# FPGA_IO.net
KiCad netlist of a schematic drawn in Altium Designer
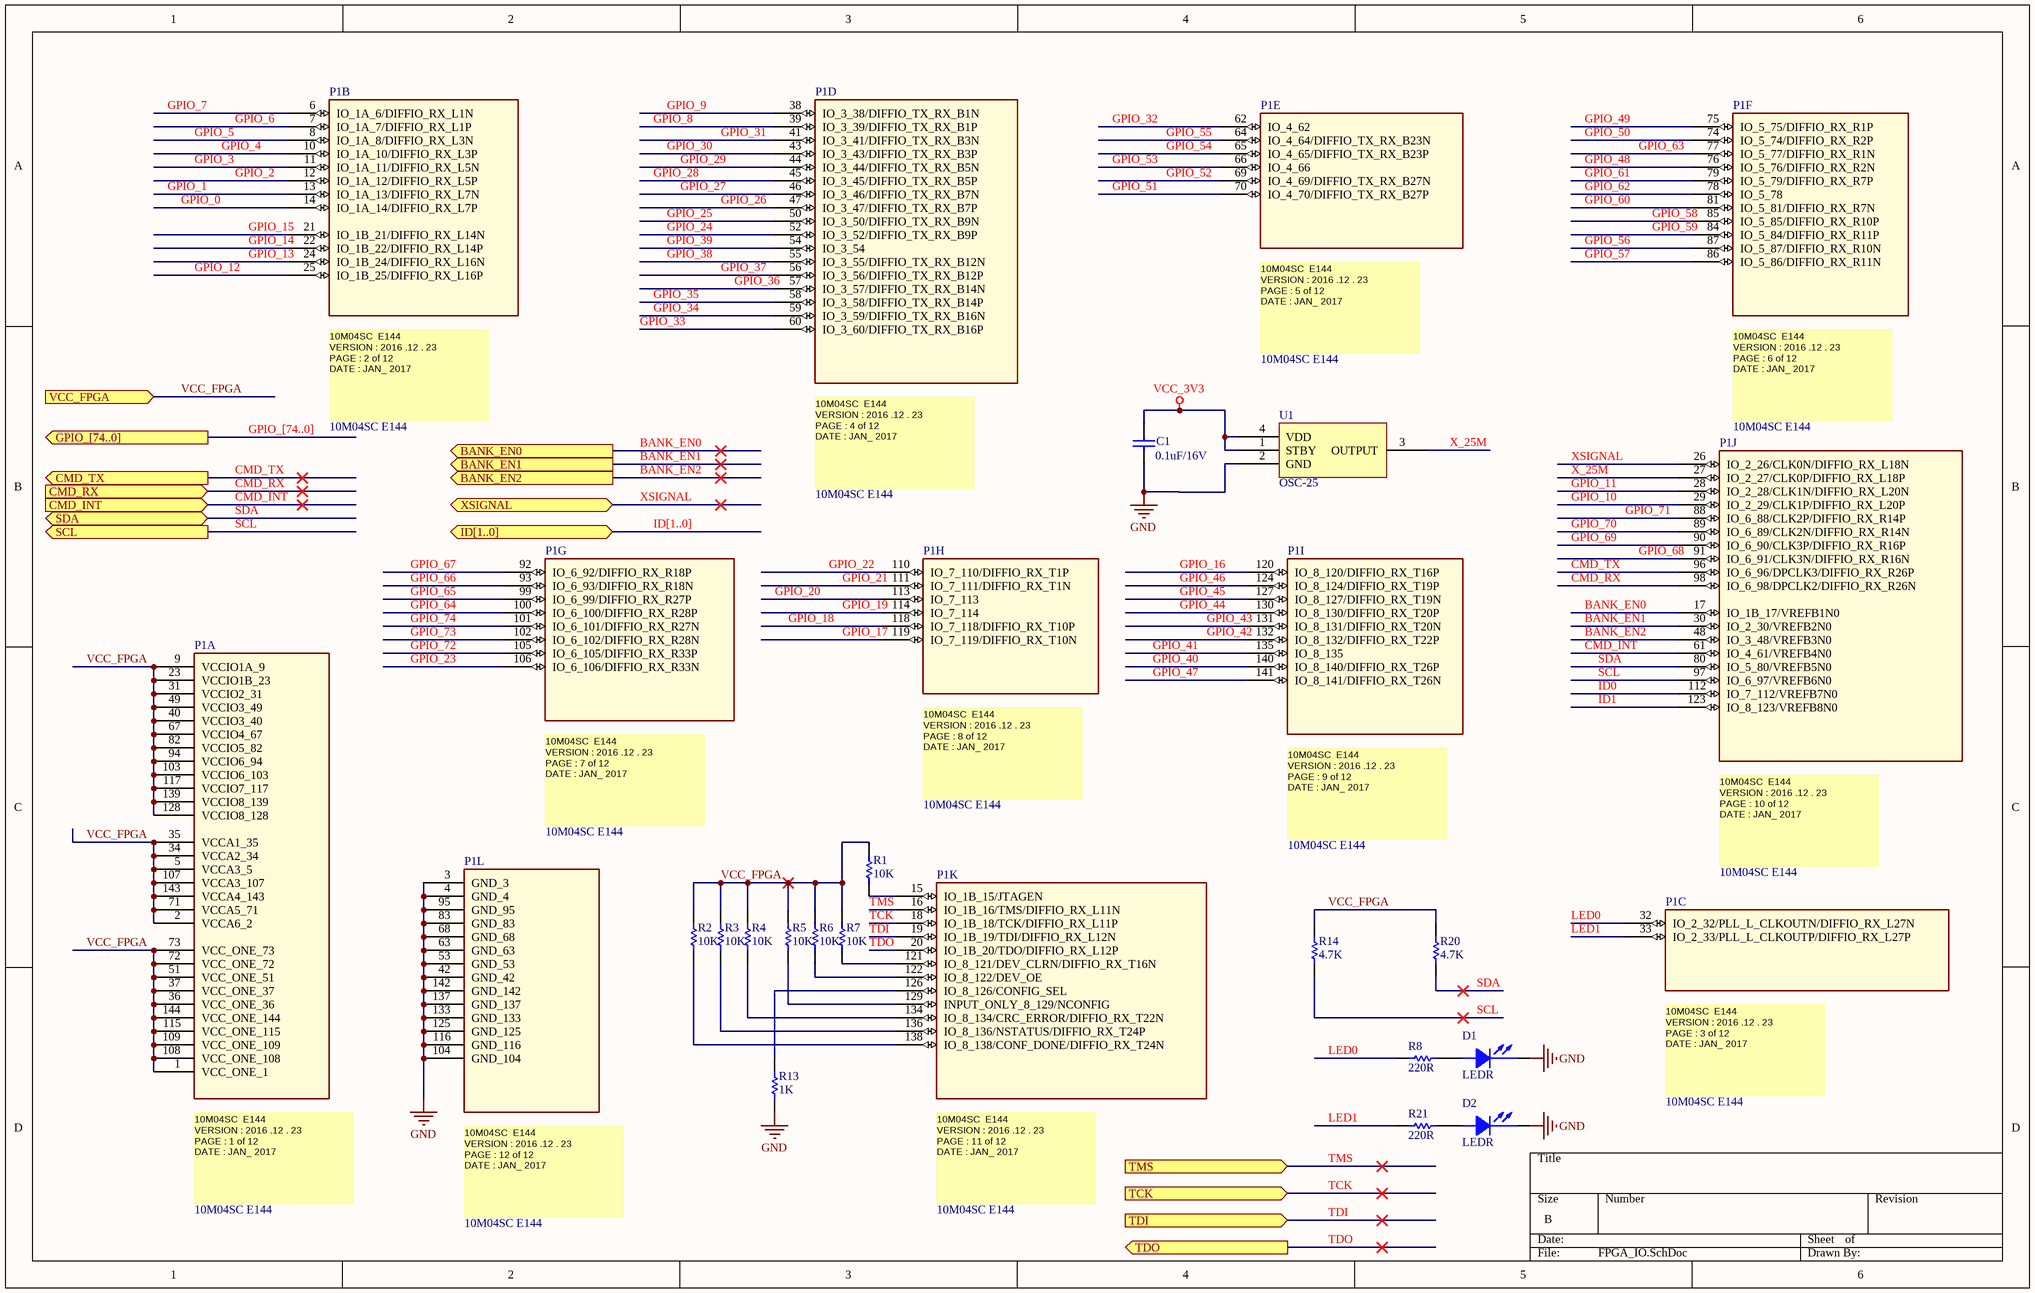
[diagram p0: FPGA_IO.SchDoc]

(export (version "E")
  (design (tool "Eeschema 10.0.6"))
  (components
    (comp (ref "C1")
      (value "0.1uF/16V")
      (footprint "0603C")
      (description "Multilayer Ceramic Capacitors MLCC - SMD/SMT 0603 16VDC 0.1uF 10% X7R AEC-Q200")
      (fields (field (name "MFR") "Taiyo Yuden") (field (name "MFR PART NO") "EMK107B7104KAHT"))
      (libsource (lib "Miscellaneous Devices") (part "Cap"))
    )
    (comp (ref "D1")
      (value "LEDR")
      (footprint "LED_0603")
      (description "Standard LEDs - SMD Red 631nm 14mcd 5mA")
      (fields (field (name "MFR") "Lite-On") (field (name "MFR PART NO") "LTST-C193KRKT-5A"))
      (libsource (lib "de20") (part "LED"))
    )
    (comp (ref "D2")
      (value "LEDR")
      (footprint "LED_0603")
      (description "Standard LEDs - SMD Red 631nm 14mcd 5mA")
      (fields (field (name "MFR") "Lite-On") (field (name "MFR PART NO") "LTST-C193KRKT-5A"))
      (libsource (lib "de20") (part "LED"))
    )
    (comp (ref "P1")
      (value "10M04SC E144")
      (footprint "10M04SCE144C8G")
      (description "FPGA - Field Programmable Gate Array non-volatile FPGA, 101 I/O, 144EQFP")
      (fields (field (name "MFR") "Intel / Altera") (field (name "MFR PART NO") "10M04SCE144C8G"))
      (libsource (lib "10m04sc_Library") (part "10M04SC E144"))
    )
    (comp (ref "R1")
      (value "10K")
      (footprint "0603R")
      (description "Thick Film Resistors - SMD 0603 10Kohms 1% Anti-Sulfur AEC-Q200")
      (fields (field (name "MFR") "ROHM Semiconductor") (field (name "MFR PART NO") "SFR03EZPF1002"))
      (libsource (lib "Miscellaneous Devices") (part "Res1"))
    )
    (comp (ref "R2")
      (value "10K")
      (footprint "0603R")
      (description "Thick Film Resistors - SMD 0603 10Kohms 1% Anti-Sulfur AEC-Q200")
      (fields (field (name "MFR") "ROHM Semiconductor") (field (name "MFR PART NO") "SFR03EZPF1002"))
      (libsource (lib "Miscellaneous Devices") (part "Res1"))
    )
    (comp (ref "R3")
      (value "10K")
      (footprint "0603R")
      (description "Thick Film Resistors - SMD 0603 10Kohms 1% Anti-Sulfur AEC-Q200")
      (fields (field (name "MFR") "ROHM Semiconductor") (field (name "MFR PART NO") "SFR03EZPF1002"))
      (libsource (lib "Miscellaneous Devices") (part "Res1"))
    )
    (comp (ref "R4")
      (value "10K")
      (footprint "0603R")
      (description "Thick Film Resistors - SMD 0603 10Kohms 1% Anti-Sulfur AEC-Q200")
      (fields (field (name "MFR") "ROHM Semiconductor") (field (name "MFR PART NO") "SFR03EZPF1002"))
      (libsource (lib "Miscellaneous Devices") (part "Res1"))
    )
    (comp (ref "R5")
      (value "10K")
      (footprint "0603R")
      (description "Thick Film Resistors - SMD 0603 10Kohms 1% Anti-Sulfur AEC-Q200")
      (fields (field (name "MFR") "ROHM Semiconductor") (field (name "MFR PART NO") "SFR03EZPF1002"))
      (libsource (lib "Miscellaneous Devices") (part "Res1"))
    )
    (comp (ref "R6")
      (value "10K")
      (footprint "0603R")
      (description "Thick Film Resistors - SMD 0603 10Kohms 1% Anti-Sulfur AEC-Q200")
      (fields (field (name "MFR") "ROHM Semiconductor") (field (name "MFR PART NO") "SFR03EZPF1002"))
      (libsource (lib "Miscellaneous Devices") (part "Res1"))
    )
    (comp (ref "R7")
      (value "10K")
      (footprint "0603R")
      (description "Thick Film Resistors - SMD 0603 10Kohms 1% Anti-Sulfur AEC-Q200")
      (fields (field (name "MFR") "ROHM Semiconductor") (field (name "MFR PART NO") "SFR03EZPF1002"))
      (libsource (lib "Miscellaneous Devices") (part "Res1"))
    )
    (comp (ref "R8")
      (value "220R")
      (footprint "0603R")
      (description "Thick Film Resistors - SMD 1/10Watt 220ohms 5% Commercial Use")
      (fields (field (name "MFR") "Vishay / Dale") (field (name "MFR PART NO") "CRCW0603220RJNEAC"))
      (libsource (lib "Miscellaneous Devices") (part "Res1"))
    )
    (comp (ref "R13")
      (value "1K")
      (footprint "0603R")
      (description "Resistor")
      (fields (field (name "MFR") "Vishay / Dale") (field (name "MFR PART NO") "CRCW06031K00FKEAC"))
      (libsource (lib "Miscellaneous Devices") (part "Res1"))
    )
    (comp (ref "R14")
      (value "4.7K")
      (footprint "0603R")
      (description "Thick Film Resistors - SMD 1/10Watt 4.7Kohms 5% Commercial Use")
      (fields (field (name "MFR") "Vishay / Dale") (field (name "MFR PART NO") "CRCW06034K70JNEAC"))
      (libsource (lib "Miscellaneous Devices") (part "Res1"))
    )
    (comp (ref "R20")
      (value "4.7K")
      (footprint "0603R")
      (description "Thick Film Resistors - SMD 1/10Watt 4.7Kohms 5% Commercial Use")
      (fields (field (name "MFR") "Vishay / Dale") (field (name "MFR PART NO") "CRCW06034K70JNEAC"))
      (libsource (lib "Miscellaneous Devices") (part "Res1"))
    )
    (comp (ref "R21")
      (value "220R")
      (footprint "0603R")
      (description "Thick Film Resistors - SMD 1/10Watt 220ohms 5% Commercial Use")
      (fields (field (name "MFR") "Vishay / Dale") (field (name "MFR PART NO") "CRCW0603220RJNEAC"))
      (libsource (lib "Miscellaneous Devices") (part "Res1"))
    )
    (comp (ref "U1")
      (value "OSC-25")
      (footprint "ASE-25.000MHZ-LC-T")
      (description "Standard Clock Oscillators 25.0 MHZ 3.3V 50PPM SMD 32")
      (fields (field (name "MFR") "ABRACON") (field (name "MFR PART NO") "ASE-25.000MHZ-LC-T"))
      (libsource (lib "Schlib1") (part "CRYSTAL"))
    )
  )
  (nets
    (net (code "1") (name "/BANK_EN0") (class "Default")
      (node (ref "P1") (pin "17") (pinfunction "IO_1B_17/VREFB1N0_17") (pintype "bidirectional"))
    )
    (net (code "2") (name "/BANK_EN1") (class "Default")
      (node (ref "P1") (pin "30") (pinfunction "IO_2_30/VREFB2N0_30") (pintype "bidirectional"))
    )
    (net (code "3") (name "/BANK_EN2") (class "Default")
      (node (ref "P1") (pin "48") (pinfunction "IO_3_48/VREFB3N0_48") (pintype "bidirectional"))
    )
    (net (code "4") (name "/CMD_INT") (class "Default")
      (node (ref "P1") (pin "61") (pinfunction "IO_4_61/VREFB4N0_61") (pintype "bidirectional"))
    )
    (net (code "5") (name "/CMD_RX") (class "Default")
      (node (ref "P1") (pin "98") (pinfunction "IO_6_98/DPCLK2/DIFFIO_RX_R26N_98") (pintype "bidirectional"))
    )
    (net (code "6") (name "/CMD_TX") (class "Default")
      (node (ref "P1") (pin "96") (pinfunction "IO_6_96/DPCLK3/DIFFIO_RX_R26P_96") (pintype "bidirectional"))
    )
    (net (code "7") (name "/GPIO_0") (class "Default")
      (node (ref "P1") (pin "14") (pinfunction "IO_1A_14/DIFFIO_RX_L7P_14") (pintype "bidirectional"))
    )
    (net (code "8") (name "/GPIO_1") (class "Default")
      (node (ref "P1") (pin "13") (pinfunction "IO_1A_13/DIFFIO_RX_L7N_13") (pintype "bidirectional"))
    )
    (net (code "9") (name "/GPIO_2") (class "Default")
      (node (ref "P1") (pin "12") (pinfunction "IO_1A_12/DIFFIO_RX_L5P_12") (pintype "bidirectional"))
    )
    (net (code "10") (name "/GPIO_3") (class "Default")
      (node (ref "P1") (pin "11") (pinfunction "IO_1A_11/DIFFIO_RX_L5N_11") (pintype "bidirectional"))
    )
    (net (code "11") (name "/GPIO_4") (class "Default")
      (node (ref "P1") (pin "10") (pinfunction "IO_1A_10/DIFFIO_RX_L3P_10") (pintype "bidirectional"))
    )
    (net (code "12") (name "/GPIO_5") (class "Default")
      (node (ref "P1") (pin "8") (pinfunction "IO_1A_8/DIFFIO_RX_L3N_8") (pintype "bidirectional"))
    )
    (net (code "13") (name "/GPIO_6") (class "Default")
      (node (ref "P1") (pin "7") (pinfunction "IO_1A_7/DIFFIO_RX_L1P_7") (pintype "bidirectional"))
    )
    (net (code "14") (name "/GPIO_7") (class "Default")
      (node (ref "P1") (pin "6") (pinfunction "IO_1A_6/DIFFIO_RX_L1N_6") (pintype "bidirectional"))
    )
    (net (code "15") (name "/GPIO_8") (class "Default")
      (node (ref "P1") (pin "39") (pinfunction "IO_3_39/DIFFIO_TX_RX_B1P_39") (pintype "bidirectional"))
    )
    (net (code "16") (name "/GPIO_9") (class "Default")
      (node (ref "P1") (pin "38") (pinfunction "IO_3_38/DIFFIO_TX_RX_B1N_38") (pintype "bidirectional"))
    )
    (net (code "17") (name "/GPIO_10") (class "Default")
      (node (ref "P1") (pin "29") (pinfunction "IO_2_29/CLK1P/DIFFIO_RX_L20P_29") (pintype "bidirectional"))
    )
    (net (code "18") (name "/GPIO_11") (class "Default")
      (node (ref "P1") (pin "28") (pinfunction "IO_2_28/CLK1N/DIFFIO_RX_L20N_28") (pintype "bidirectional"))
    )
    (net (code "19") (name "/GPIO_12") (class "Default")
      (node (ref "P1") (pin "25") (pinfunction "IO_1B_25/DIFFIO_RX_L16P_25") (pintype "bidirectional"))
    )
    (net (code "20") (name "/GPIO_13") (class "Default")
      (node (ref "P1") (pin "24") (pinfunction "IO_1B_24/DIFFIO_RX_L16N_24") (pintype "bidirectional"))
    )
    (net (code "21") (name "/GPIO_14") (class "Default")
      (node (ref "P1") (pin "22") (pinfunction "IO_1B_22/DIFFIO_RX_L14P_22") (pintype "bidirectional"))
    )
    (net (code "22") (name "/GPIO_15") (class "Default")
      (node (ref "P1") (pin "21") (pinfunction "IO_1B_21/DIFFIO_RX_L14N_21") (pintype "bidirectional"))
    )
    (net (code "23") (name "/GPIO_16") (class "Default")
      (node (ref "P1") (pin "120") (pinfunction "IO_8_120/DIFFIO_RX_T16P_120") (pintype "bidirectional"))
    )
    (net (code "24") (name "/GPIO_17") (class "Default")
      (node (ref "P1") (pin "119") (pinfunction "IO_7_119/DIFFIO_RX_T10N_119") (pintype "bidirectional"))
    )
    (net (code "25") (name "/GPIO_18") (class "Default")
      (node (ref "P1") (pin "118") (pinfunction "IO_7_118/DIFFIO_RX_T10P_118") (pintype "bidirectional"))
    )
    (net (code "26") (name "/GPIO_19") (class "Default")
      (node (ref "P1") (pin "114") (pinfunction "IO_7_114_114") (pintype "bidirectional"))
    )
    (net (code "27") (name "/GPIO_20") (class "Default")
      (node (ref "P1") (pin "113") (pinfunction "IO_7_113_113") (pintype "bidirectional"))
    )
    (net (code "28") (name "/GPIO_21") (class "Default")
      (node (ref "P1") (pin "111") (pinfunction "IO_7_111/DIFFIO_RX_T1N_111") (pintype "bidirectional"))
    )
    (net (code "29") (name "/GPIO_22") (class "Default")
      (node (ref "P1") (pin "110") (pinfunction "IO_7_110/DIFFIO_RX_T1P_110") (pintype "bidirectional"))
    )
    (net (code "30") (name "/GPIO_23") (class "Default")
      (node (ref "P1") (pin "106") (pinfunction "IO_6_106/DIFFIO_RX_R33N_106") (pintype "bidirectional"))
    )
    (net (code "31") (name "/GPIO_24") (class "Default")
      (node (ref "P1") (pin "52") (pinfunction "IO_3_52/DIFFIO_TX_RX_B9P_52") (pintype "bidirectional"))
    )
    (net (code "32") (name "/GPIO_25") (class "Default")
      (node (ref "P1") (pin "50") (pinfunction "IO_3_50/DIFFIO_TX_RX_B9N_50") (pintype "bidirectional"))
    )
    (net (code "33") (name "/GPIO_26") (class "Default")
      (node (ref "P1") (pin "47") (pinfunction "IO_3_47/DIFFIO_TX_RX_B7P_47") (pintype "bidirectional"))
    )
    (net (code "34") (name "/GPIO_27") (class "Default")
      (node (ref "P1") (pin "46") (pinfunction "IO_3_46/DIFFIO_TX_RX_B7N_46") (pintype "bidirectional"))
    )
    (net (code "35") (name "/GPIO_28") (class "Default")
      (node (ref "P1") (pin "45") (pinfunction "IO_3_45/DIFFIO_TX_RX_B5P_45") (pintype "bidirectional"))
    )
    (net (code "36") (name "/GPIO_29") (class "Default")
      (node (ref "P1") (pin "44") (pinfunction "IO_3_44/DIFFIO_TX_RX_B5N_44") (pintype "bidirectional"))
    )
    (net (code "37") (name "/GPIO_30") (class "Default")
      (node (ref "P1") (pin "43") (pinfunction "IO_3_43/DIFFIO_TX_RX_B3P_43") (pintype "bidirectional"))
    )
    (net (code "38") (name "/GPIO_31") (class "Default")
      (node (ref "P1") (pin "41") (pinfunction "IO_3_41/DIFFIO_TX_RX_B3N_41") (pintype "bidirectional"))
    )
    (net (code "39") (name "/GPIO_32") (class "Default")
      (node (ref "P1") (pin "62") (pinfunction "IO_4_62_62") (pintype "bidirectional"))
    )
    (net (code "40") (name "/GPIO_33") (class "Default")
      (node (ref "P1") (pin "60") (pinfunction "IO_3_60/DIFFIO_TX_RX_B16P_60") (pintype "bidirectional"))
    )
    (net (code "41") (name "/GPIO_34") (class "Default")
      (node (ref "P1") (pin "59") (pinfunction "IO_3_59/DIFFIO_TX_RX_B16N_59") (pintype "bidirectional"))
    )
    (net (code "42") (name "/GPIO_35") (class "Default")
      (node (ref "P1") (pin "58") (pinfunction "IO_3_58/DIFFIO_TX_RX_B14P_58") (pintype "bidirectional"))
    )
    (net (code "43") (name "/GPIO_36") (class "Default")
      (node (ref "P1") (pin "57") (pinfunction "IO_3_57/DIFFIO_TX_RX_B14N_57") (pintype "bidirectional"))
    )
    (net (code "44") (name "/GPIO_37") (class "Default")
      (node (ref "P1") (pin "56") (pinfunction "IO_3_56/DIFFIO_TX_RX_B12P_56") (pintype "bidirectional"))
    )
    (net (code "45") (name "/GPIO_38") (class "Default")
      (node (ref "P1") (pin "55") (pinfunction "IO_3_55/DIFFIO_TX_RX_B12N_55") (pintype "bidirectional"))
    )
    (net (code "46") (name "/GPIO_39") (class "Default")
      (node (ref "P1") (pin "54") (pinfunction "IO_3_54_54") (pintype "bidirectional"))
    )
    (net (code "47") (name "/GPIO_40") (class "Default")
      (node (ref "P1") (pin "140") (pinfunction "IO_8_140/DIFFIO_RX_T26P_140") (pintype "bidirectional"))
    )
    (net (code "48") (name "/GPIO_41") (class "Default")
      (node (ref "P1") (pin "135") (pinfunction "IO_8_135_135") (pintype "bidirectional"))
    )
    (net (code "49") (name "/GPIO_42") (class "Default")
      (node (ref "P1") (pin "132") (pinfunction "IO_8_132/DIFFIO_RX_T22P_132") (pintype "bidirectional"))
    )
    (net (code "50") (name "/GPIO_43") (class "Default")
      (node (ref "P1") (pin "131") (pinfunction "IO_8_131/DIFFIO_RX_T20N_131") (pintype "bidirectional"))
    )
    (net (code "51") (name "/GPIO_44") (class "Default")
      (node (ref "P1") (pin "130") (pinfunction "IO_8_130/DIFFIO_RX_T20P_130") (pintype "bidirectional"))
    )
    (net (code "52") (name "/GPIO_45") (class "Default")
      (node (ref "P1") (pin "127") (pinfunction "IO_8_127/DIFFIO_RX_T19N_127") (pintype "bidirectional"))
    )
    (net (code "53") (name "/GPIO_46") (class "Default")
      (node (ref "P1") (pin "124") (pinfunction "IO_8_124/DIFFIO_RX_T19P_124") (pintype "bidirectional"))
    )
    (net (code "54") (name "/GPIO_47") (class "Default")
      (node (ref "P1") (pin "141") (pinfunction "IO_8_141/DIFFIO_RX_T26N_141") (pintype "bidirectional"))
    )
    (net (code "55") (name "/GPIO_48") (class "Default")
      (node (ref "P1") (pin "76") (pinfunction "IO_5_76/DIFFIO_RX_R2N_76") (pintype "bidirectional"))
    )
    (net (code "56") (name "/GPIO_49") (class "Default")
      (node (ref "P1") (pin "75") (pinfunction "IO_5_75/DIFFIO_RX_R1P_75") (pintype "bidirectional"))
    )
    (net (code "57") (name "/GPIO_50") (class "Default")
      (node (ref "P1") (pin "74") (pinfunction "IO_5_74/DIFFIO_RX_R2P_74") (pintype "bidirectional"))
    )
    (net (code "58") (name "/GPIO_51") (class "Default")
      (node (ref "P1") (pin "70") (pinfunction "IO_4_70/DIFFIO_TX_RX_B27P_70") (pintype "bidirectional"))
    )
    (net (code "59") (name "/GPIO_52") (class "Default")
      (node (ref "P1") (pin "69") (pinfunction "IO_4_69/DIFFIO_TX_RX_B27N_69") (pintype "bidirectional"))
    )
    (net (code "60") (name "/GPIO_53") (class "Default")
      (node (ref "P1") (pin "66") (pinfunction "IO_4_66_66") (pintype "bidirectional"))
    )
    (net (code "61") (name "/GPIO_54") (class "Default")
      (node (ref "P1") (pin "65") (pinfunction "IO_4_65/DIFFIO_TX_RX_B23P_65") (pintype "bidirectional"))
    )
    (net (code "62") (name "/GPIO_55") (class "Default")
      (node (ref "P1") (pin "64") (pinfunction "IO_4_64/DIFFIO_TX_RX_B23N_64") (pintype "bidirectional"))
    )
    (net (code "63") (name "/GPIO_56") (class "Default")
      (node (ref "P1") (pin "87") (pinfunction "IO_5_87/DIFFIO_RX_R10N_87") (pintype "bidirectional"))
    )
    (net (code "64") (name "/GPIO_57") (class "Default")
      (node (ref "P1") (pin "86") (pinfunction "IO_5_86/DIFFIO_RX_R11N_86") (pintype "bidirectional"))
    )
    (net (code "65") (name "/GPIO_58") (class "Default")
      (node (ref "P1") (pin "85") (pinfunction "IO_5_85/DIFFIO_RX_R10P_85") (pintype "bidirectional"))
    )
    (net (code "66") (name "/GPIO_59") (class "Default")
      (node (ref "P1") (pin "84") (pinfunction "IO_5_84/DIFFIO_RX_R11P_84") (pintype "bidirectional"))
    )
    (net (code "67") (name "/GPIO_60") (class "Default")
      (node (ref "P1") (pin "81") (pinfunction "IO_5_81/DIFFIO_RX_R7N_81") (pintype "bidirectional"))
    )
    (net (code "68") (name "/GPIO_61") (class "Default")
      (node (ref "P1") (pin "79") (pinfunction "IO_5_79/DIFFIO_RX_R7P_79") (pintype "bidirectional"))
    )
    (net (code "69") (name "/GPIO_62") (class "Default")
      (node (ref "P1") (pin "78") (pinfunction "IO_5_78_78") (pintype "bidirectional"))
    )
    (net (code "70") (name "/GPIO_63") (class "Default")
      (node (ref "P1") (pin "77") (pinfunction "IO_5_77/DIFFIO_RX_R1N_77") (pintype "bidirectional"))
    )
    (net (code "71") (name "/GPIO_64") (class "Default")
      (node (ref "P1") (pin "100") (pinfunction "IO_6_100/DIFFIO_RX_R28P_100") (pintype "bidirectional"))
    )
    (net (code "72") (name "/GPIO_65") (class "Default")
      (node (ref "P1") (pin "99") (pinfunction "IO_6_99/DIFFIO_RX_R27P_99") (pintype "bidirectional"))
    )
    (net (code "73") (name "/GPIO_66") (class "Default")
      (node (ref "P1") (pin "93") (pinfunction "IO_6_93/DIFFIO_RX_R18N_93") (pintype "bidirectional"))
    )
    (net (code "74") (name "/GPIO_67") (class "Default")
      (node (ref "P1") (pin "92") (pinfunction "IO_6_92/DIFFIO_RX_R18P_92") (pintype "bidirectional"))
    )
    (net (code "75") (name "/GPIO_68") (class "Default")
      (node (ref "P1") (pin "91") (pinfunction "IO_6_91/CLK3N/DIFFIO_RX_R16N_91") (pintype "bidirectional"))
    )
    (net (code "76") (name "/GPIO_69") (class "Default")
      (node (ref "P1") (pin "90") (pinfunction "IO_6_90/CLK3P/DIFFIO_RX_R16P_90") (pintype "bidirectional"))
    )
    (net (code "77") (name "/GPIO_70") (class "Default")
      (node (ref "P1") (pin "89") (pinfunction "IO_6_89/CLK2N/DIFFIO_RX_R14N_89") (pintype "bidirectional"))
    )
    (net (code "78") (name "/GPIO_71") (class "Default")
      (node (ref "P1") (pin "88") (pinfunction "IO_6_88/CLK2P/DIFFIO_RX_R14P_88") (pintype "bidirectional"))
    )
    (net (code "79") (name "/GPIO_72") (class "Default")
      (node (ref "P1") (pin "105") (pinfunction "IO_6_105/DIFFIO_RX_R33P_105") (pintype "bidirectional"))
    )
    (net (code "80") (name "/GPIO_73") (class "Default")
      (node (ref "P1") (pin "102") (pinfunction "IO_6_102/DIFFIO_RX_R28N_102") (pintype "bidirectional"))
    )
    (net (code "81") (name "/GPIO_74") (class "Default")
      (node (ref "P1") (pin "101") (pinfunction "IO_6_101/DIFFIO_RX_R27N_101") (pintype "bidirectional"))
    )
    (net (code "83") (name "/ID0") (class "Default")
      (node (ref "P1") (pin "112") (pinfunction "IO_7_112/VREFB7N0_112") (pintype "bidirectional"))
    )
    (net (code "84") (name "/ID1") (class "Default")
      (node (ref "P1") (pin "123") (pinfunction "IO_8_123/VREFB8N0_123") (pintype "bidirectional"))
    )
    (net (code "86") (name "/LED0") (class "Default")
      (node (ref "P1") (pin "32") (pinfunction "IO_2_32/PLL_L_CLKOUTN/DIFFIO_RX_L27N_32") (pintype "bidirectional"))
      (node (ref "R8") (pin "2") (pinfunction "2_2") (pintype "passive"))
    )
    (net (code "87") (name "/LED1") (class "Default")
      (node (ref "P1") (pin "33") (pinfunction "IO_2_33/PLL_L_CLKOUTP/DIFFIO_RX_L27P_33") (pintype "bidirectional"))
      (node (ref "R21") (pin "2") (pinfunction "2_2") (pintype "passive"))
    )
    (net (code "88") (name "/SCL") (class "Default")
      (node (ref "P1") (pin "97") (pinfunction "IO_6_97/VREFB6N0_97") (pintype "bidirectional"))
      (node (ref "R14") (pin "1") (pinfunction "1_1") (pintype "passive"))
    )
    (net (code "89") (name "/SDA") (class "Default")
      (node (ref "P1") (pin "80") (pinfunction "IO_5_80/VREFB5N0_80") (pintype "bidirectional"))
      (node (ref "R20") (pin "1") (pinfunction "1_1") (pintype "passive"))
    )
    (net (code "90") (name "/TCK") (class "Default")
      (node (ref "P1") (pin "18") (pinfunction "IO_1B_18/TCK/DIFFIO_RX_L11P_18") (pintype "bidirectional"))
    )
    (net (code "91") (name "/TDI") (class "Default")
      (node (ref "P1") (pin "19") (pinfunction "IO_1B_19/TDI/DIFFIO_RX_L12N_19") (pintype "bidirectional"))
    )
    (net (code "92") (name "/TDO") (class "Default")
      (node (ref "P1") (pin "20") (pinfunction "IO_1B_20/TDO/DIFFIO_RX_L12P_20") (pintype "bidirectional"))
    )
    (net (code "93") (name "/TMS") (class "Default")
      (node (ref "P1") (pin "16") (pinfunction "IO_1B_16/TMS/DIFFIO_RX_L11N_16") (pintype "bidirectional"))
    )
    (net (code "94") (name "/VCC_FPGA") (class "Default")
      (node (ref "P1") (pin "1") (pinfunction "VCC_ONE_1_1") (pintype "power_in"))
      (node (ref "P1") (pin "103") (pinfunction "VCCIO6_103_103") (pintype "power_in"))
      (node (ref "P1") (pin "107") (pinfunction "VCCA3_107_107") (pintype "power_in"))
      (node (ref "P1") (pin "108") (pinfunction "VCC_ONE_108_108") (pintype "power_in"))
      (node (ref "P1") (pin "109") (pinfunction "VCC_ONE_109_109") (pintype "power_in"))
      (node (ref "P1") (pin "115") (pinfunction "VCC_ONE_115_115") (pintype "power_in"))
      (node (ref "P1") (pin "117") (pinfunction "VCCIO7_117_117") (pintype "power_in"))
      (node (ref "P1") (pin "128") (pinfunction "VCCIO8_128_128") (pintype "power_in"))
      (node (ref "P1") (pin "139") (pinfunction "VCCIO8_139_139") (pintype "power_in"))
      (node (ref "P1") (pin "143") (pinfunction "VCCA4_143_143") (pintype "power_in"))
      (node (ref "P1") (pin "144") (pinfunction "VCC_ONE_144_144") (pintype "power_in"))
      (node (ref "P1") (pin "2") (pinfunction "VCCA6_2_2") (pintype "power_in"))
      (node (ref "P1") (pin "23") (pinfunction "VCCIO1B_23_23") (pintype "power_in"))
      (node (ref "P1") (pin "31") (pinfunction "VCCIO2_31_31") (pintype "power_in"))
      (node (ref "P1") (pin "34") (pinfunction "VCCA2_34_34") (pintype "power_in"))
      (node (ref "P1") (pin "35") (pinfunction "VCCA1_35_35") (pintype "power_in"))
      (node (ref "P1") (pin "36") (pinfunction "VCC_ONE_36_36") (pintype "power_in"))
      (node (ref "P1") (pin "37") (pinfunction "VCC_ONE_37_37") (pintype "power_in"))
      (node (ref "P1") (pin "40") (pinfunction "VCCIO3_40_40") (pintype "power_in"))
      (node (ref "P1") (pin "49") (pinfunction "VCCIO3_49_49") (pintype "power_in"))
      (node (ref "P1") (pin "5") (pinfunction "VCCA3_5_5") (pintype "power_in"))
      (node (ref "P1") (pin "51") (pinfunction "VCC_ONE_51_51") (pintype "power_in"))
      (node (ref "P1") (pin "67") (pinfunction "VCCIO4_67_67") (pintype "power_in"))
      (node (ref "P1") (pin "71") (pinfunction "VCCA5_71_71") (pintype "power_in"))
      (node (ref "P1") (pin "72") (pinfunction "VCC_ONE_72_72") (pintype "power_in"))
      (node (ref "P1") (pin "73") (pinfunction "VCC_ONE_73_73") (pintype "power_in"))
      (node (ref "P1") (pin "82") (pinfunction "VCCIO5_82_82") (pintype "power_in"))
      (node (ref "P1") (pin "9") (pinfunction "VCCIO1A_9_9") (pintype "power_in"))
      (node (ref "P1") (pin "94") (pinfunction "VCCIO6_94_94") (pintype "power_in"))
      (node (ref "R1") (pin "1") (pinfunction "1_1") (pintype "passive"))
      (node (ref "R14") (pin "2") (pinfunction "2_2") (pintype "passive"))
      (node (ref "R2") (pin "1") (pinfunction "1_1") (pintype "passive"))
      (node (ref "R20") (pin "2") (pinfunction "2_2") (pintype "passive"))
      (node (ref "R3") (pin "1") (pinfunction "1_1") (pintype "passive"))
      (node (ref "R4") (pin "1") (pinfunction "1_1") (pintype "passive"))
      (node (ref "R5") (pin "1") (pinfunction "1_1") (pintype "passive"))
      (node (ref "R6") (pin "1") (pinfunction "1_1") (pintype "passive"))
      (node (ref "R7") (pin "1") (pinfunction "1_1") (pintype "passive"))
    )
    (net (code "95") (name "/XSIGNAL") (class "Default")
      (node (ref "P1") (pin "26") (pinfunction "IO_2_26/CLK0N/DIFFIO_RX_L18N_26") (pintype "bidirectional"))
    )
    (net (code "96") (name "/X_25M") (class "Default")
      (node (ref "P1") (pin "27") (pinfunction "IO_2_27/CLK0P/DIFFIO_RX_L18P_27") (pintype "bidirectional"))
      (node (ref "U1") (pin "3") (pinfunction "OUTPUT_3") (pintype "passive"))
    )
    (net (code "97") (name "GND") (class "Default")
      (node (ref "C1") (pin "1") (pinfunction "1_1") (pintype "passive"))
      (node (ref "D1") (pin "2") (pinfunction "CATHODE_2") (pintype "passive"))
      (node (ref "D2") (pin "2") (pinfunction "CATHODE_2") (pintype "passive"))
      (node (ref "P1") (pin "104") (pinfunction "GND_104_104") (pintype "power_in"))
      (node (ref "P1") (pin "116") (pinfunction "GND_116_116") (pintype "power_in"))
      (node (ref "P1") (pin "125") (pinfunction "GND_125_125") (pintype "power_in"))
      (node (ref "P1") (pin "133") (pinfunction "GND_133_133") (pintype "power_in"))
      (node (ref "P1") (pin "137") (pinfunction "GND_137_137") (pintype "power_in"))
      (node (ref "P1") (pin "142") (pinfunction "GND_142_142") (pintype "power_in"))
      (node (ref "P1") (pin "3") (pinfunction "GND_3_3") (pintype "power_in"))
      (node (ref "P1") (pin "4") (pinfunction "GND_4_4") (pintype "power_in"))
      (node (ref "P1") (pin "42") (pinfunction "GND_42_42") (pintype "power_in"))
      (node (ref "P1") (pin "53") (pinfunction "GND_53_53") (pintype "power_in"))
      (node (ref "P1") (pin "63") (pinfunction "GND_63_63") (pintype "power_in"))
      (node (ref "P1") (pin "68") (pinfunction "GND_68_68") (pintype "power_in"))
      (node (ref "P1") (pin "83") (pinfunction "GND_83_83") (pintype "power_in"))
      (node (ref "P1") (pin "95") (pinfunction "GND_95_95") (pintype "power_in"))
      (node (ref "R13") (pin "1") (pinfunction "1_1") (pintype "passive"))
      (node (ref "U1") (pin "2") (pinfunction "GND_2") (pintype "passive"))
    )
    (net (code "98") (name "Net-(D1-ANODE)") (class "Default")
      (node (ref "D1") (pin "1") (pinfunction "ANODE_1") (pintype "passive"))
      (node (ref "R8") (pin "1") (pinfunction "1_1") (pintype "passive"))
    )
    (net (code "99") (name "Net-(D2-ANODE)") (class "Default")
      (node (ref "D2") (pin "1") (pinfunction "ANODE_1") (pintype "passive"))
      (node (ref "R21") (pin "1") (pinfunction "1_1") (pintype "passive"))
    )
    (net (code "100") (name "Net-(P1K-INPUT_ONLY_8_129{slash}NCONFIG)") (class "Default")
      (node (ref "P1") (pin "129") (pinfunction "INPUT_ONLY_8_129/NCONFIG_129") (pintype "bidirectional"))
      (node (ref "R5") (pin "2") (pinfunction "2_2") (pintype "passive"))
    )
    (net (code "101") (name "Net-(P1K-IO_1B_15{slash}JTAGEN)") (class "Default")
      (node (ref "P1") (pin "15") (pinfunction "IO_1B_15/JTAGEN_15") (pintype "bidirectional"))
      (node (ref "R1") (pin "2") (pinfunction "2_2") (pintype "passive"))
    )
    (net (code "102") (name "Net-(P1K-IO_8_121{slash}DEV_CLRN{slash}DIFFIO_RX_T16N)") (class "Default")
      (node (ref "P1") (pin "121") (pinfunction "IO_8_121/DEV_CLRN/DIFFIO_RX_T16N_121") (pintype "bidirectional"))
      (node (ref "R7") (pin "2") (pinfunction "2_2") (pintype "passive"))
    )
    (net (code "103") (name "Net-(P1K-IO_8_122{slash}DEV_OE)") (class "Default")
      (node (ref "P1") (pin "122") (pinfunction "IO_8_122/DEV_OE_122") (pintype "bidirectional"))
      (node (ref "R6") (pin "2") (pinfunction "2_2") (pintype "passive"))
    )
    (net (code "104") (name "Net-(P1K-IO_8_126{slash}CONFIG_SEL)") (class "Default")
      (node (ref "P1") (pin "126") (pinfunction "IO_8_126/CONFIG_SEL_126") (pintype "bidirectional"))
      (node (ref "R13") (pin "2") (pinfunction "2_2") (pintype "passive"))
    )
    (net (code "105") (name "Net-(P1K-IO_8_134{slash}CRC_ERROR{slash}DIFFIO_RX_T22N)") (class "Default")
      (node (ref "P1") (pin "134") (pinfunction "IO_8_134/CRC_ERROR/DIFFIO_RX_T22N_134") (pintype "bidirectional"))
      (node (ref "R4") (pin "2") (pinfunction "2_2") (pintype "passive"))
    )
    (net (code "106") (name "Net-(P1K-IO_8_136{slash}NSTATUS{slash}DIFFIO_RX_T24P)") (class "Default")
      (node (ref "P1") (pin "136") (pinfunction "IO_8_136/NSTATUS/DIFFIO_RX_T24P_136") (pintype "bidirectional"))
      (node (ref "R3") (pin "2") (pinfunction "2_2") (pintype "passive"))
    )
    (net (code "107") (name "Net-(P1K-IO_8_138{slash}CONF_DONE{slash}DIFFIO_RX_T24N)") (class "Default")
      (node (ref "P1") (pin "138") (pinfunction "IO_8_138/CONF_DONE/DIFFIO_RX_T24N_138") (pintype "bidirectional"))
      (node (ref "R2") (pin "2") (pinfunction "2_2") (pintype "passive"))
    )
    (net (code "108") (name "VCC_3V3") (class "Default")
      (node (ref "C1") (pin "2") (pinfunction "2_2") (pintype "passive"))
      (node (ref "U1") (pin "1") (pinfunction "STBY_1") (pintype "passive"))
      (node (ref "U1") (pin "4") (pinfunction "VDD_4") (pintype "passive"))
    )
  )
)
